# OSSC_HDMI_Audio_v1_3_A4.net
KiCad netlist of a schematic drawn in EAGLE
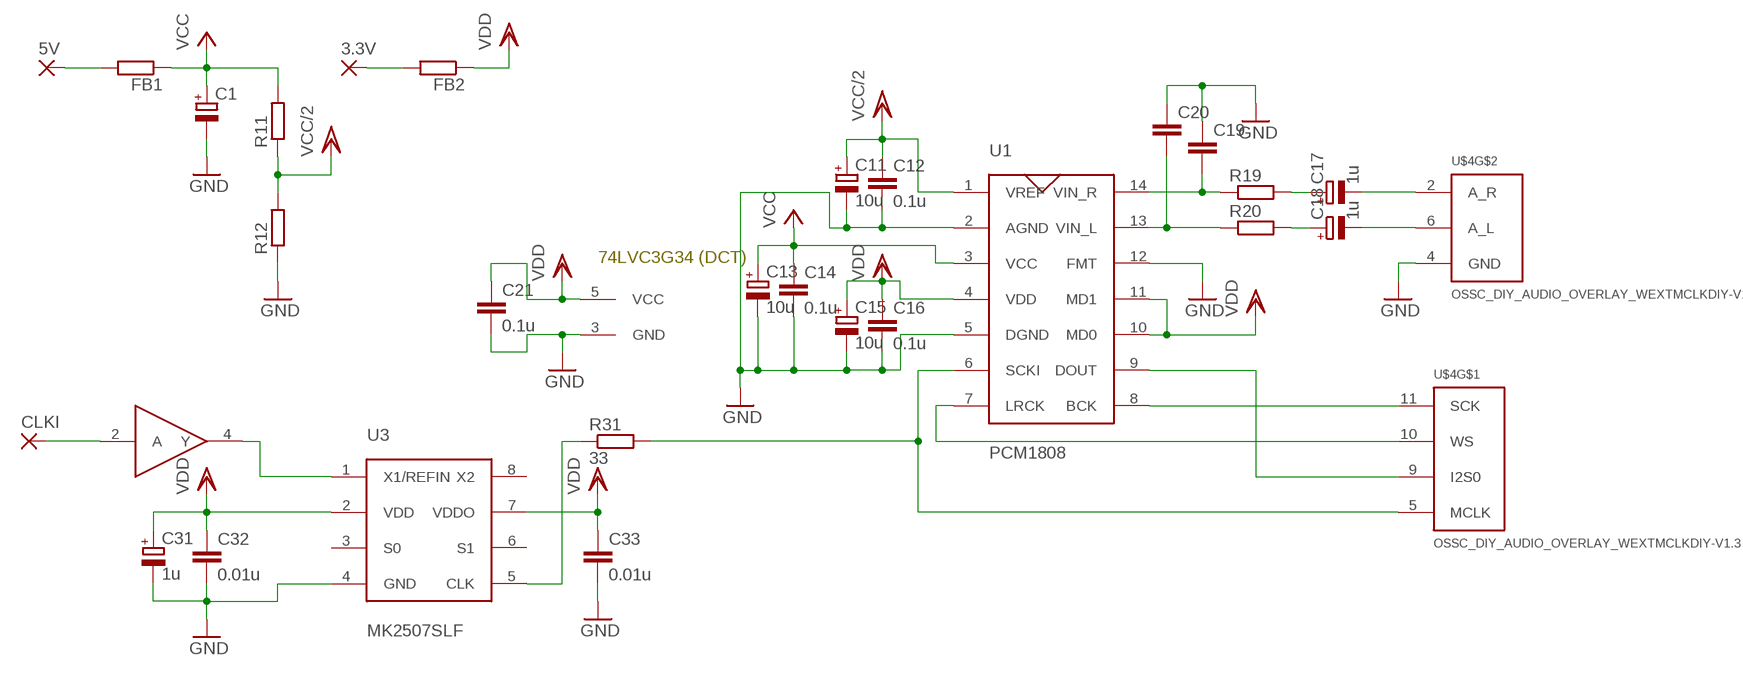
[diagram p0: schematic, sheet 1]

(export (version "E")
  (design (tool "Eeschema 10.0.6"))
  (components
    (comp (ref "3.3V")
      (value "SMD2")
      (footprint "eagle-import:SMD1,27-2,54")
      (libsource (lib "eagle-import") (part "SMD2"))
    )
    (comp (ref "5V")
      (value "SMD2")
      (footprint "eagle-import:SMD1,27-2,54")
      (libsource (lib "eagle-import") (part "SMD2"))
    )
    (comp (ref "C1")
      (value "CPOL-EUSMCC")
      (footprint "eagle-import:SMC_C")
      (libsource (lib "eagle-import") (part "CPOL-EUSMCC"))
    )
    (comp (ref "C11")
      (value "10u")
      (footprint "eagle-import:SMC_A")
      (libsource (lib "eagle-import") (part "CPOL-EUSMCA"))
    )
    (comp (ref "C12")
      (value "0.1u")
      (footprint "eagle-import:C0603")
      (libsource (lib "eagle-import") (part "C-EUC0603"))
    )
    (comp (ref "C13")
      (value "10u")
      (footprint "eagle-import:SMC_A")
      (libsource (lib "eagle-import") (part "CPOL-EUSMCA"))
    )
    (comp (ref "C14")
      (value "0.1u")
      (footprint "eagle-import:C0603")
      (libsource (lib "eagle-import") (part "C-EUC0603"))
    )
    (comp (ref "C15")
      (value "10u")
      (footprint "eagle-import:SMC_A")
      (libsource (lib "eagle-import") (part "CPOL-EUSMCA"))
    )
    (comp (ref "C16")
      (value "0.1u")
      (footprint "eagle-import:C0603")
      (libsource (lib "eagle-import") (part "C-EUC0603"))
    )
    (comp (ref "C17")
      (value "1u")
      (footprint "eagle-import:SMC_A")
      (libsource (lib "eagle-import") (part "CPOL-EUSMCA"))
    )
    (comp (ref "C18")
      (value "1u")
      (footprint "eagle-import:SMC_A")
      (libsource (lib "eagle-import") (part "CPOL-EUSMCA"))
    )
    (comp (ref "C19")
      (value "C-EUC0603")
      (footprint "eagle-import:C0603")
      (libsource (lib "eagle-import") (part "C-EUC0603"))
    )
    (comp (ref "C20")
      (value "C-EUC0603")
      (footprint "eagle-import:C0603")
      (libsource (lib "eagle-import") (part "C-EUC0603"))
    )
    (comp (ref "C21")
      (value "0.1u")
      (footprint "eagle-import:C0603")
      (libsource (lib "eagle-import") (part "C-EUC0603"))
    )
    (comp (ref "C31")
      (value "1u")
      (footprint "eagle-import:SMC_A")
      (libsource (lib "eagle-import") (part "CPOL-EUSMCA"))
    )
    (comp (ref "C32")
      (value "0.01u")
      (footprint "eagle-import:C0603")
      (libsource (lib "eagle-import") (part "C-EUC0603"))
    )
    (comp (ref "C33")
      (value "0.01u")
      (footprint "eagle-import:C0603")
      (libsource (lib "eagle-import") (part "C-EUC0603"))
    )
    (comp (ref "CLKI")
      (value "SMD2")
      (footprint "eagle-import:SMD1,27-2,54")
      (libsource (lib "eagle-import") (part "SMD2"))
    )
    (comp (ref "FB1")
      (value "R-EU_R0603")
      (footprint "eagle-import:R0603")
      (libsource (lib "eagle-import") (part "R-EU_R0603"))
    )
    (comp (ref "FB2")
      (value "R-EU_R0603")
      (footprint "eagle-import:R0603")
      (libsource (lib "eagle-import") (part "R-EU_R0603"))
    )
    (comp (ref "R11")
      (value "R-EU_R0603")
      (footprint "eagle-import:R0603")
      (libsource (lib "eagle-import") (part "R-EU_R0603"))
    )
    (comp (ref "R12")
      (value "R-EU_R0603")
      (footprint "eagle-import:R0603")
      (libsource (lib "eagle-import") (part "R-EU_R0603"))
    )
    (comp (ref "R19")
      (value "R-EU_R0603")
      (footprint "eagle-import:R0603")
      (libsource (lib "eagle-import") (part "R-EU_R0603"))
    )
    (comp (ref "R20")
      (value "R-EU_R0603")
      (footprint "eagle-import:R0603")
      (libsource (lib "eagle-import") (part "R-EU_R0603"))
    )
    (comp (ref "R31")
      (value "33")
      (footprint "eagle-import:R0603")
      (libsource (lib "eagle-import") (part "R-EU_R0603"))
    )
    (comp (ref "U$4")
      (value "OSSC_DIY_AUDIO_OVERLAY_WEXTMCLKDIY-V1.3")
      (footprint "eagle-import:OSSC_OVERLAY_V1.3_WEXTMCLK")
      (libsource (lib "eagle-import") (part "OSSC_DIY_AUDIO_OVERLAY_WEXTMCLKDIY-V1.3"))
    )
    (comp (ref "U1")
      (value "PCM1808")
      (footprint "eagle-import:PCM1808")
      (libsource (lib "eagle-import") (part "PCM1808"))
    )
    (comp (ref "U2")
      (value "74LVC1G34")
      (footprint "eagle-import:74LVC1G34DCK")
      (libsource (lib "eagle-import") (part "74LVC1G34"))
    )
    (comp (ref "U3")
      (value "MK2507SLF")
      (footprint "eagle-import:SOIC8")
      (libsource (lib "eagle-import") (part "MK2507SLF"))
    )
  )
  (nets
    (net (code "1") (name "GND") (class "Default")
      (node (ref "C1") (pin "-") (pinfunction "-_-") (pintype "passive"))
      (node (ref "C11") (pin "-") (pinfunction "-_-") (pintype "passive"))
      (node (ref "C12") (pin "2") (pinfunction "2_2") (pintype "passive"))
      (node (ref "C13") (pin "-") (pinfunction "-_-") (pintype "passive"))
      (node (ref "C14") (pin "2") (pinfunction "2_2") (pintype "passive"))
      (node (ref "C15") (pin "-") (pinfunction "-_-") (pintype "passive"))
      (node (ref "C16") (pin "2") (pinfunction "2_2") (pintype "passive"))
      (node (ref "C19") (pin "1") (pinfunction "1_1") (pintype "passive"))
      (node (ref "C20") (pin "1") (pinfunction "1_1") (pintype "passive"))
      (node (ref "C21") (pin "2") (pinfunction "2_2") (pintype "passive"))
      (node (ref "C31") (pin "-") (pinfunction "-_-") (pintype "passive"))
      (node (ref "C32") (pin "2") (pinfunction "2_2") (pintype "passive"))
      (node (ref "C33") (pin "2") (pinfunction "2_2") (pintype "passive"))
      (node (ref "R12") (pin "1") (pinfunction "1_1") (pintype "passive"))
      (node (ref "U$4") (pin "4") (pinfunction "GND_4") (pintype "bidirectional"))
      (node (ref "U1") (pin "12") (pinfunction "FMT_12") (pintype "bidirectional"))
      (node (ref "U1") (pin "2") (pinfunction "AGND_2") (pintype "bidirectional"))
      (node (ref "U1") (pin "5") (pinfunction "DGND_5") (pintype "bidirectional"))
      (node (ref "U2") (pin "3") (pinfunction "GND_3") (pintype "bidirectional"))
      (node (ref "U3") (pin "4") (pinfunction "GND_4") (pintype "bidirectional"))
    )
    (net (code "2") (name "Net-(3.3V-P)") (class "Default")
      (node (ref "3.3V") (pin "1") (pinfunction "P_1") (pintype "passive"))
      (node (ref "FB2") (pin "2") (pinfunction "2_2") (pintype "passive"))
    )
    (net (code "3") (name "Net-(5V-P)") (class "Default")
      (node (ref "5V") (pin "1") (pinfunction "P_1") (pintype "passive"))
      (node (ref "FB1") (pin "2") (pinfunction "2_2") (pintype "passive"))
    )
    (net (code "4") (name "Net-(C17-Pad+)") (class "Default")
      (node (ref "C17") (pin "+") (pinfunction "+_+") (pintype "passive"))
      (node (ref "R19") (pin "2") (pinfunction "2_2") (pintype "passive"))
    )
    (net (code "5") (name "Net-(C18-Pad+)") (class "Default")
      (node (ref "C18") (pin "+") (pinfunction "+_+") (pintype "passive"))
      (node (ref "R20") (pin "2") (pinfunction "2_2") (pintype "passive"))
    )
    (net (code "6") (name "Net-(CLKI-P)") (class "Default")
      (node (ref "CLKI") (pin "1") (pinfunction "P_1") (pintype "passive"))
      (node (ref "U2") (pin "2") (pinfunction "A_2") (pintype "bidirectional"))
    )
    (net (code "7") (name "Net-(U$4A-I2S0)") (class "Default")
      (node (ref "U$4") (pin "9") (pinfunction "I2S0_9") (pintype "bidirectional"))
      (node (ref "U1") (pin "9") (pinfunction "DOUT_9") (pintype "bidirectional"))
    )
    (net (code "8") (name "Net-(U$4A-MCLK)") (class "Default")
      (node (ref "R31") (pin "2") (pinfunction "2_2") (pintype "passive"))
      (node (ref "U$4") (pin "5") (pinfunction "MCLK_5") (pintype "bidirectional"))
      (node (ref "U1") (pin "6") (pinfunction "SCKI_6") (pintype "bidirectional"))
    )
    (net (code "9") (name "Net-(U$4A-SCK)") (class "Default")
      (node (ref "U$4") (pin "11") (pinfunction "SCK_11") (pintype "bidirectional"))
      (node (ref "U1") (pin "8") (pinfunction "BCK_8") (pintype "bidirectional"))
    )
    (net (code "10") (name "Net-(U$4A-WS)") (class "Default")
      (node (ref "U$4") (pin "10") (pinfunction "WS_10") (pintype "bidirectional"))
      (node (ref "U1") (pin "7") (pinfunction "LRCK_7") (pintype "bidirectional"))
    )
    (net (code "11") (name "Net-(U$4B-A_L)") (class "Default")
      (node (ref "C18") (pin "-") (pinfunction "-_-") (pintype "passive"))
      (node (ref "U$4") (pin "6") (pinfunction "A_L_6") (pintype "bidirectional"))
    )
    (net (code "12") (name "Net-(U$4B-A_R)") (class "Default")
      (node (ref "C17") (pin "-") (pinfunction "-_-") (pintype "passive"))
      (node (ref "U$4") (pin "2") (pinfunction "A_R_2") (pintype "bidirectional"))
    )
    (net (code "13") (name "Net-(U1-VIN_L)") (class "Default")
      (node (ref "C20") (pin "2") (pinfunction "2_2") (pintype "passive"))
      (node (ref "R20") (pin "1") (pinfunction "1_1") (pintype "passive"))
      (node (ref "U1") (pin "13") (pinfunction "VIN_L_13") (pintype "bidirectional"))
    )
    (net (code "14") (name "Net-(U1-VIN_R)") (class "Default")
      (node (ref "C19") (pin "2") (pinfunction "2_2") (pintype "passive"))
      (node (ref "R19") (pin "1") (pinfunction "1_1") (pintype "passive"))
      (node (ref "U1") (pin "14") (pinfunction "VIN_R_14") (pintype "bidirectional"))
    )
    (net (code "15") (name "Net-(U2A-Y)") (class "Default")
      (node (ref "U2") (pin "4") (pinfunction "Y_4") (pintype "bidirectional"))
      (node (ref "U3") (pin "1") (pinfunction "X1/REFIN_1") (pintype "bidirectional"))
    )
    (net (code "16") (name "Net-(U3-CLK)") (class "Default")
      (node (ref "R31") (pin "1") (pinfunction "1_1") (pintype "passive"))
      (node (ref "U3") (pin "5") (pinfunction "CLK_5") (pintype "bidirectional"))
    )
    (net (code "17") (name "VCC") (class "Default")
      (node (ref "C1") (pin "+") (pinfunction "+_+") (pintype "passive"))
      (node (ref "C13") (pin "+") (pinfunction "+_+") (pintype "passive"))
      (node (ref "C14") (pin "1") (pinfunction "1_1") (pintype "passive"))
      (node (ref "FB1") (pin "1") (pinfunction "1_1") (pintype "passive"))
      (node (ref "R11") (pin "2") (pinfunction "2_2") (pintype "passive"))
      (node (ref "U1") (pin "3") (pinfunction "VCC_3") (pintype "bidirectional"))
    )
    (net (code "18") (name "VCC{slash}2") (class "Default")
      (node (ref "C11") (pin "+") (pinfunction "+_+") (pintype "passive"))
      (node (ref "C12") (pin "1") (pinfunction "1_1") (pintype "passive"))
      (node (ref "R11") (pin "1") (pinfunction "1_1") (pintype "passive"))
      (node (ref "R12") (pin "2") (pinfunction "2_2") (pintype "passive"))
      (node (ref "U1") (pin "1") (pinfunction "VREF_1") (pintype "bidirectional"))
    )
    (net (code "19") (name "VDD") (class "Default")
      (node (ref "C15") (pin "+") (pinfunction "+_+") (pintype "passive"))
      (node (ref "C16") (pin "1") (pinfunction "1_1") (pintype "passive"))
      (node (ref "C21") (pin "1") (pinfunction "1_1") (pintype "passive"))
      (node (ref "C31") (pin "+") (pinfunction "+_+") (pintype "passive"))
      (node (ref "C32") (pin "1") (pinfunction "1_1") (pintype "passive"))
      (node (ref "C33") (pin "1") (pinfunction "1_1") (pintype "passive"))
      (node (ref "FB2") (pin "1") (pinfunction "1_1") (pintype "passive"))
      (node (ref "U1") (pin "10") (pinfunction "MD0_10") (pintype "bidirectional"))
      (node (ref "U1") (pin "11") (pinfunction "MD1_11") (pintype "bidirectional"))
      (node (ref "U1") (pin "4") (pinfunction "VDD_4") (pintype "bidirectional"))
      (node (ref "U2") (pin "5") (pinfunction "VCC_5") (pintype "bidirectional"))
      (node (ref "U3") (pin "2") (pinfunction "VDD_2") (pintype "bidirectional"))
      (node (ref "U3") (pin "7") (pinfunction "VDDO_7") (pintype "bidirectional"))
    )
    (net (code "20") (name "unconnected-(U3-S0-Pad3)") (class "Default")
      (node (ref "U3") (pin "3") (pinfunction "S0_3") (pintype "bidirectional"))
    )
    (net (code "21") (name "unconnected-(U3-S1-Pad6)") (class "Default")
      (node (ref "U3") (pin "6") (pinfunction "S1_6") (pintype "bidirectional"))
    )
    (net (code "22") (name "unconnected-(U3-X2-Pad8)") (class "Default")
      (node (ref "U3") (pin "8") (pinfunction "X2_8") (pintype "bidirectional"))
    )
  )
)
